# MiniSumoMotors.net
KiCad netlist of a schematic drawn in EAGLE
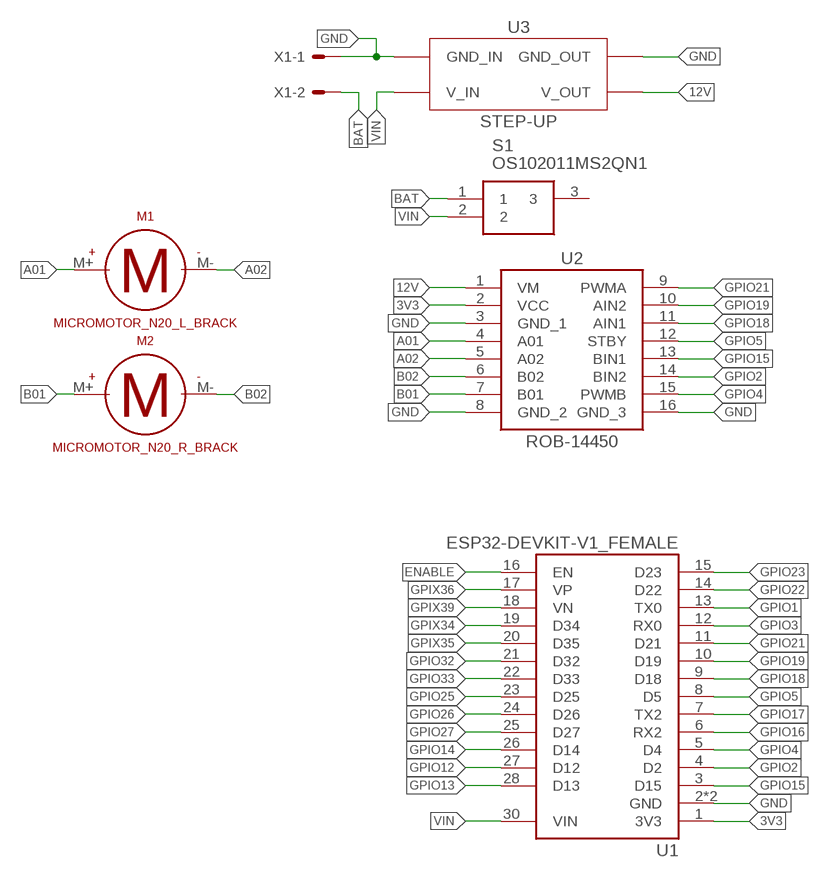
[diagram p0: schematic, sheet 1]

(export (version "E")
  (design (tool "Eeschema 10.0.6"))
  (components
    (comp (ref "M1")
      (value "MICROMOTOR_N20_L_BRACK")
      (footprint "eagle-import:MICROMOTOR-L_BRACK")
      (libsource (lib "eagle-import") (part "MICROMOTOR_N20_L_BRACK"))
    )
    (comp (ref "M2")
      (value "MICROMOTOR_N20_R_BRACK")
      (footprint "eagle-import:MICROMOTOR-R_BRACK")
      (libsource (lib "eagle-import") (part "MICROMOTOR_N20_R_BRACK"))
    )
    (comp (ref "S1")
      (value "OS102011MS2QN1")
      (footprint "eagle-import:OS102011MA1QN1")
      (fields (field (name "RS_PART_NUMBER") "7874864"))
      (libsource (lib "eagle-import") (part "OS102011MS2QN1"))
    )
    (comp (ref "U1")
      (value "ESP32-DEVKIT-V1_FEMALE")
      (footprint "eagle-import:MODULE_ESP32_DEVKIT_V1_FEMALE")
      (libsource (lib "eagle-import") (part "ESP32-DEVKIT-V1_FEMALE"))
    )
    (comp (ref "U2")
      (value "ROB-14450")
      (footprint "eagle-import:ROB14450")
      (fields (field (name "MOUSER_PART_NUMBER") "474-ROB-14450"))
      (libsource (lib "eagle-import") (part "ROB-14450"))
    )
    (comp (ref "U3")
      (value "STEP-UP")
      (footprint "eagle-import:STEP-UP")
      (libsource (lib "eagle-import") (part "STEP-UP"))
    )
    (comp (ref "X1")
      (value "22-23-2021")
      (footprint "eagle-import:22-23-2021")
      (fields (field (name "MF") "MOLEX"))
      (libsource (lib "eagle-import") (part "22-23-2021"))
    )
  )
  (nets
    (net (code "1") (name "3V3") (class "Default")
      (node (ref "U1") (pin "1") (pinfunction "3V3_1") (pintype "output"))
      (node (ref "U2") (pin "2") (pinfunction "VCC_2") (pintype "bidirectional"))
    )
    (net (code "2") (name "12V") (class "Default")
      (node (ref "U2") (pin "1") (pinfunction "VM_1") (pintype "bidirectional"))
      (node (ref "U3") (pin "V_OUT") (pinfunction "V_OUT_V_OUT") (pintype "bidirectional"))
    )
    (net (code "3") (name "A01") (class "Default")
      (node (ref "M1") (pin "M+") (pinfunction "M+_M+") (pintype "bidirectional"))
      (node (ref "U2") (pin "4") (pinfunction "A01_4") (pintype "bidirectional"))
    )
    (net (code "4") (name "A02") (class "Default")
      (node (ref "M1") (pin "M-") (pinfunction "M-_M-") (pintype "bidirectional"))
      (node (ref "U2") (pin "5") (pinfunction "A02_5") (pintype "bidirectional"))
    )
    (net (code "5") (name "B01") (class "Default")
      (node (ref "M2") (pin "M+") (pinfunction "M+_M+") (pintype "bidirectional"))
      (node (ref "U2") (pin "7") (pinfunction "B01_7") (pintype "bidirectional"))
    )
    (net (code "6") (name "B02") (class "Default")
      (node (ref "M2") (pin "M-") (pinfunction "M-_M-") (pintype "bidirectional"))
      (node (ref "U2") (pin "6") (pinfunction "B02_6") (pintype "bidirectional"))
    )
    (net (code "7") (name "BAT") (class "Default")
      (node (ref "S1") (pin "1") (pinfunction "1_1") (pintype "bidirectional"))
      (node (ref "X1") (pin "2") (pinfunction "S_2") (pintype "passive"))
    )
    (net (code "8") (name "ENABLE") (class "Default")
      (node (ref "U1") (pin "16") (pinfunction "EN_16") (pintype "input"))
    )
    (net (code "9") (name "GND") (class "Default")
      (node (ref "U1") (pin "2") (pinfunction "GND_2") (pintype "power_in"))
      (node (ref "U1") (pin "29") (pinfunction "GND_29") (pintype "power_in"))
      (node (ref "U2") (pin "16") (pinfunction "GND_3_16") (pintype "bidirectional"))
      (node (ref "U2") (pin "3") (pinfunction "GND_1_3") (pintype "bidirectional"))
      (node (ref "U2") (pin "8") (pinfunction "GND_2_8") (pintype "bidirectional"))
      (node (ref "U3") (pin "GND_IN") (pinfunction "GND_IN_GND_IN") (pintype "bidirectional"))
      (node (ref "U3") (pin "GND_OUT") (pinfunction "GND_OUT_GND_OUT") (pintype "bidirectional"))
      (node (ref "X1") (pin "1") (pinfunction "S_1") (pintype "passive"))
    )
    (net (code "10") (name "GPIO1") (class "Default")
      (node (ref "U1") (pin "13") (pinfunction "TX0_13") (pintype "output"))
    )
    (net (code "11") (name "GPIO2") (class "Default")
      (node (ref "U1") (pin "4") (pinfunction "D2_4") (pintype "bidirectional"))
      (node (ref "U2") (pin "14") (pinfunction "BIN2_14") (pintype "bidirectional"))
    )
    (net (code "12") (name "GPIO3") (class "Default")
      (node (ref "U1") (pin "12") (pinfunction "RX0_12") (pintype "input"))
    )
    (net (code "13") (name "GPIO4") (class "Default")
      (node (ref "U1") (pin "5") (pinfunction "D4_5") (pintype "bidirectional"))
      (node (ref "U2") (pin "15") (pinfunction "PWMB_15") (pintype "bidirectional"))
    )
    (net (code "14") (name "GPIO5") (class "Default")
      (node (ref "U1") (pin "8") (pinfunction "D5_8") (pintype "bidirectional"))
      (node (ref "U2") (pin "12") (pinfunction "STBY_12") (pintype "bidirectional"))
    )
    (net (code "15") (name "GPIO12") (class "Default")
      (node (ref "U1") (pin "27") (pinfunction "D12_27") (pintype "bidirectional"))
    )
    (net (code "16") (name "GPIO13") (class "Default")
      (node (ref "U1") (pin "28") (pinfunction "D13_28") (pintype "bidirectional"))
    )
    (net (code "17") (name "GPIO14") (class "Default")
      (node (ref "U1") (pin "26") (pinfunction "D14_26") (pintype "bidirectional"))
    )
    (net (code "18") (name "GPIO15") (class "Default")
      (node (ref "U1") (pin "3") (pinfunction "D15_3") (pintype "bidirectional"))
      (node (ref "U2") (pin "13") (pinfunction "BIN1_13") (pintype "bidirectional"))
    )
    (net (code "19") (name "GPIO16") (class "Default")
      (node (ref "U1") (pin "6") (pinfunction "RX2_6") (pintype "input"))
    )
    (net (code "20") (name "GPIO17") (class "Default")
      (node (ref "U1") (pin "7") (pinfunction "TX2_7") (pintype "output"))
    )
    (net (code "21") (name "GPIO18") (class "Default")
      (node (ref "U1") (pin "9") (pinfunction "D18_9") (pintype "bidirectional"))
      (node (ref "U2") (pin "11") (pinfunction "AIN1_11") (pintype "bidirectional"))
    )
    (net (code "22") (name "GPIO19") (class "Default")
      (node (ref "U1") (pin "10") (pinfunction "D19_10") (pintype "bidirectional"))
      (node (ref "U2") (pin "10") (pinfunction "AIN2_10") (pintype "bidirectional"))
    )
    (net (code "23") (name "GPIO21") (class "Default")
      (node (ref "U1") (pin "11") (pinfunction "D21_11") (pintype "bidirectional"))
      (node (ref "U2") (pin "9") (pinfunction "PWMA_9") (pintype "bidirectional"))
    )
    (net (code "24") (name "GPIO22") (class "Default")
      (node (ref "U1") (pin "14") (pinfunction "D22_14") (pintype "bidirectional"))
    )
    (net (code "25") (name "GPIO23") (class "Default")
      (node (ref "U1") (pin "15") (pinfunction "D23_15") (pintype "bidirectional"))
    )
    (net (code "26") (name "GPIO25") (class "Default")
      (node (ref "U1") (pin "23") (pinfunction "D25_23") (pintype "bidirectional"))
    )
    (net (code "27") (name "GPIO26") (class "Default")
      (node (ref "U1") (pin "24") (pinfunction "D26_24") (pintype "bidirectional"))
    )
    (net (code "28") (name "GPIO27") (class "Default")
      (node (ref "U1") (pin "25") (pinfunction "D27_25") (pintype "bidirectional"))
    )
    (net (code "29") (name "GPIO32") (class "Default")
      (node (ref "U1") (pin "21") (pinfunction "D32_21") (pintype "bidirectional"))
    )
    (net (code "30") (name "GPIO33") (class "Default")
      (node (ref "U1") (pin "22") (pinfunction "D33_22") (pintype "bidirectional"))
    )
    (net (code "31") (name "GPIX34") (class "Default")
      (node (ref "U1") (pin "19") (pinfunction "D34_19") (pintype "bidirectional"))
    )
    (net (code "32") (name "GPIX35") (class "Default")
      (node (ref "U1") (pin "20") (pinfunction "D35_20") (pintype "bidirectional"))
    )
    (net (code "33") (name "GPIX36") (class "Default")
      (node (ref "U1") (pin "17") (pinfunction "VP_17") (pintype "bidirectional"))
    )
    (net (code "34") (name "GPIX39") (class "Default")
      (node (ref "U1") (pin "18") (pinfunction "VN_18") (pintype "bidirectional"))
    )
    (net (code "35") (name "VIN") (class "Default")
      (node (ref "S1") (pin "2") (pinfunction "2_2") (pintype "bidirectional"))
      (node (ref "U1") (pin "30") (pinfunction "VIN_30") (pintype "input"))
      (node (ref "U3") (pin "V_IN") (pinfunction "V_IN_V_IN") (pintype "bidirectional"))
    )
    (net (code "36") (name "unconnected-(S1-Pad3)") (class "Default")
      (node (ref "S1") (pin "3") (pinfunction "3_3") (pintype "bidirectional"))
    )
  )
)
